# Power_System.net
KiCad netlist of a schematic drawn in Altium Designer
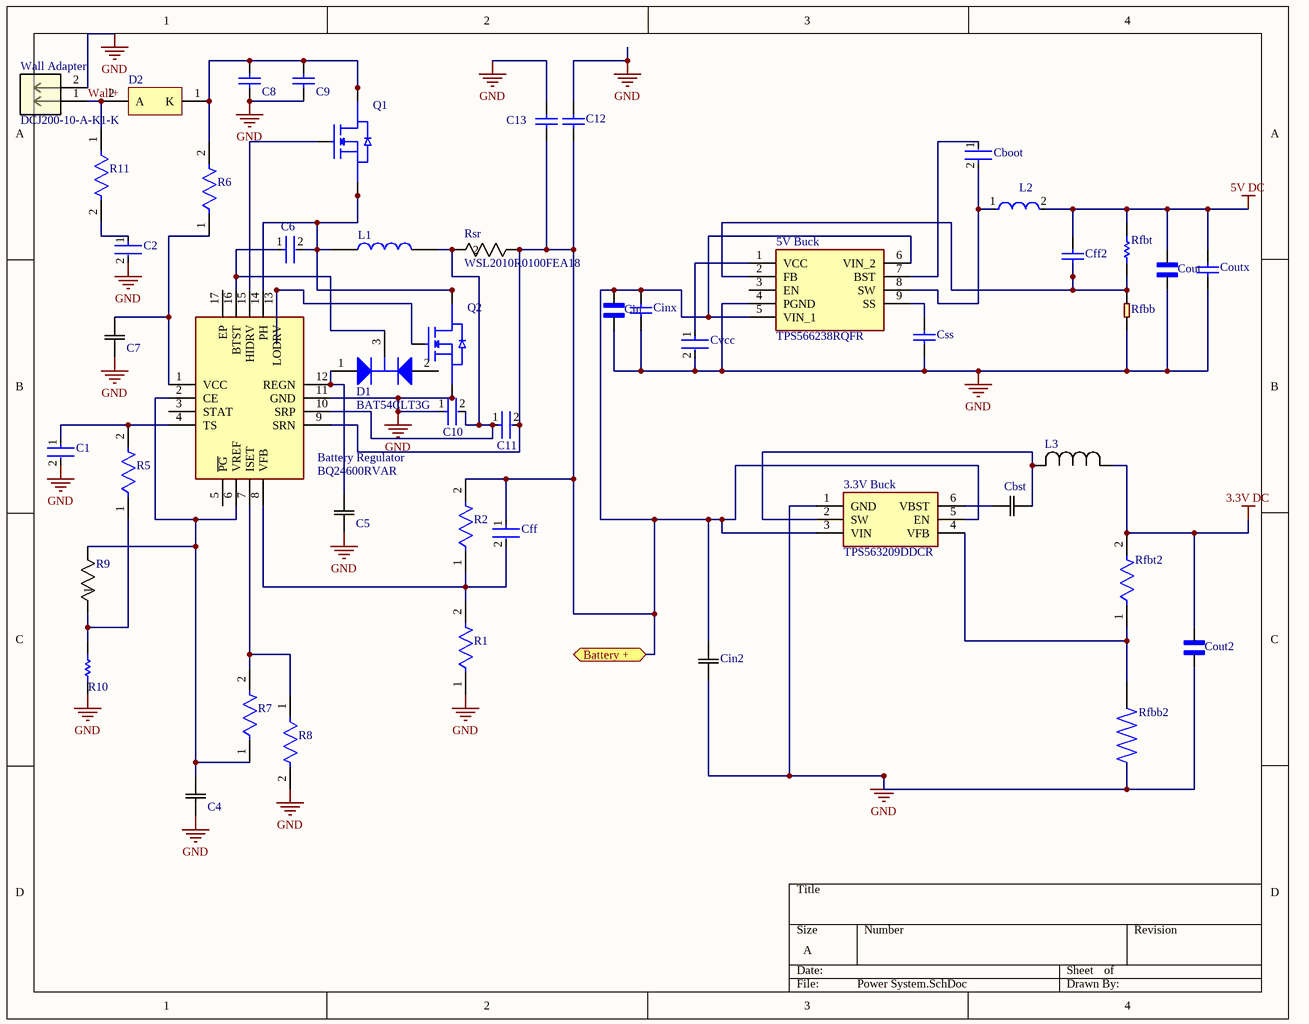
[diagram p0: Power System.SchDoc]

(export (version "E")
  (design (tool "Eeschema 10.0.6"))
  (components
    (comp (ref "3.3V Buck")
      (value "TPS563209DDCR")
      (footprint "SOT95P280X110-6N")
      (description "17 V Input, 3A Synchronous Step-Down Regulator in SOT-23")
      (fields (field (name "MOUSER PART NUMBER") "595-TPS563209DDCR"))
      (libsource (lib "William Jachimiak") (part "TPS563209DDCR"))
    )
    (comp (ref "5V Buck")
      (value "TPS566238RQFR")
      (footprint "TPS566238RQFR")
      (fields (field (name "MOUSER PART NUMBER") "595-TPS566238RQFR"))
      (libsource (lib "William Jachimiak") (part "TPS566238RQFR"))
    )
    (comp (ref "Battery Regulator")
      (value "BQ24600RVAR")
      (footprint "QFN50P350X350X100-17N-D")
      (description "Synchronous Switch-Mode Li-Ion or Li-Polymer Battery Charger")
      (fields (field (name "MOUSER PART NUMBER") "595-BQ24600RVAR"))
      (libsource (lib "William Jachimiak") (part "BQ24600RVAR"))
    )
    (comp (ref "C1")
      (value "C0603C104K4RAC7411")
      (footprint "FP-C0603C-CF-MFG")
      (description "CAP CER 0.1UF 16V X7R 0603")
      (fields (field (name "MANUFACTURER") "KEMET") (field (name "TOLERANCE") "0.1"))
      (libsource (lib "Altium Content Vault") (part "b4654b650e69147ec39a6b967a45e02"))
    )
    (comp (ref "C2")
      (value "CGA5L3X7R1H225K160AB")
      (footprint "FP-CGA5L-0_3-0_1-IPC_C")
      (description "Cap Ceramic 2.2uF 50V X7R 10% Pad SMD 1206 +125°C Automotive T/R")
      (fields (field (name "TOLERANCE") "10%"))
      (libsource (lib "Altium Content Vault") (part "b4654b650e69147ec39a6b967a45e02"))
    )
    (comp (ref "C4")
      (value "C1206C105K4RACTU")
      (footprint "CAPC340180_140N_KEM")
      (description "SMD Comm X7R, Ceramic, 1 uF, 10%, 16 VDC, X7R, SMD, MLCC, Temperature Stable, Class II, 1206")
      (fields (field (name "COPYRIGHT") "Copyright (C) 2025 Ultra Librarian. All rights reserved."))
      (libsource (lib "C1206C105K4RACTU") (part "C1206C105K4RACTU"))
    )
    (comp (ref "C5")
      (value "C1206C105K4RACTU")
      (footprint "CAPC340180_140N_KEM")
      (description "SMD Comm X7R, Ceramic, 1 uF, 10%, 16 VDC, X7R, SMD, MLCC, Temperature Stable, Class II, 1206")
      (fields (field (name "COPYRIGHT") "Copyright (C) 2025 Ultra Librarian. All rights reserved."))
      (libsource (lib "C1206C105K4RACTU") (part "C1206C105K4RACTU"))
    )
    (comp (ref "C6")
      (value "C0603C104K4RAC7411")
      (footprint "FP-C0603C-CF-MFG")
      (description "CAP CER 0.1UF 16V X7R 0603")
      (fields (field (name "MANUFACTURER") "KEMET") (field (name "TOLERANCE") "0.1"))
      (libsource (lib "Altium Content Vault") (part "b4654b650e69147ec39a6b967a45e02"))
    )
    (comp (ref "C7")
      (value "GRM32ER71H105KA01L")
      (footprint "CAP_GRM32ED_MUR")
      (description "No Description Available")
      (fields (field (name "COPYRIGHT") "Copyright (C) 2025 Ultra Librarian. All rights reserved."))
      (libsource (lib "GRM32ER71H105KA01L") (part "GRM32ER71H105KA01L"))
    )
    (comp (ref "C8")
      (value "GRM32ER7YA106KA12L")
      (footprint "CAPC3225X270X30LL30")
      (description "Chip Capacitor, 10 uF, +/- 10%, 35 V, -55 to 125 degC, 1210 (3225 Metric), RoHS, Tape and Reel")
      (fields (field (name "MANUFACTURER") "Murata"))
      (libsource (lib "Altium Content Vault") (part "CAP-NP-2"))
    )
    (comp (ref "C9")
      (value "GRM32ER7YA106KA12L")
      (footprint "CAPC3225X270X30LL30")
      (description "Chip Capacitor, 10 uF, +/- 10%, 35 V, -55 to 125 degC, 1210 (3225 Metric), RoHS, Tape and Reel")
      (fields (field (name "MANUFACTURER") "Murata"))
      (libsource (lib "Altium Content Vault") (part "CAP-NP-2"))
    )
    (comp (ref "C10")
      (value "C0603C104K5RACTU")
      (footprint "FP-C0603C-CF-MFG")
      (description "CAP CER 0.1UF 50V X7R 0603")
      (fields (field (name "TOLERANCE") "0.1") (field (name "MANUFACTURER") "KEMET"))
      (libsource (lib "Altium Content Vault") (part "b4654b650e69147ec39a6b967a45e02"))
    )
    (comp (ref "C11")
      (value "C0603C104K4RAC7411")
      (footprint "FP-C0603C-CF-MFG")
      (description "CAP CER 0.1UF 16V X7R 0603")
      (fields (field (name "MANUFACTURER") "KEMET") (field (name "TOLERANCE") "0.1"))
      (libsource (lib "Altium Content Vault") (part "b4654b650e69147ec39a6b967a45e02"))
    )
    (comp (ref "C12")
      (value "GRM32ER7YA106KA12L")
      (footprint "CAPC3225X270X30LL30")
      (description "Chip Capacitor, 10 uF, +/- 10%, 35 V, -55 to 125 degC, 1210 (3225 Metric), RoHS, Tape and Reel")
      (fields (field (name "MANUFACTURER") "Murata"))
      (libsource (lib "Altium Content Vault") (part "CAP-NP-2"))
    )
    (comp (ref "C13")
      (value "GRM32ER7YA106KA12L")
      (footprint "CAPC3225X270X30LL30")
      (description "Chip Capacitor, 10 uF, +/- 10%, 35 V, -55 to 125 degC, 1210 (3225 Metric), RoHS, Tape and Reel")
      (fields (field (name "MANUFACTURER") "Murata"))
      (libsource (lib "Altium Content Vault") (part "CAP-NP-2"))
    )
    (comp (ref "Cboot")
      (value "GRM155R71C104KA88D")
      (footprint "FP-GRM15-MFG")
      (description "CAP CER 0.1UF 16V X7R 0402")
      (fields
        (field (name "TOLERANCE") "10%")
        (field (name "OCTOPART") "https://octopart.com/grm155r71c104ka88d-murata-196880")
      )
      (libsource (lib "Altium Content Vault") (part "236180d848d6139a670b325ea6854c9"))
    )
    (comp (ref "Cbst")
      (value "08053C104KAT2A")
      (footprint "CAP_X7R_0805_AVX")
      (description "Description")
      (fields (field (name "COPYRIGHT") "Copyright (C) 2025 Ultra Librarian. All rights reserved."))
      (libsource (lib "08053C104KAT2A") (part "08053C104KAT2A"))
    )
    (comp (ref "Cff")
      (value "DE11XRB220KN4AR01F")
      (footprint "FP-DE1_D6_T5_F10_d0_6-0_0-MFG")
      (description "Cap Ceramic Disc 22pF 10% 500VAC Thru-Hole 6.0x5.0x10.0 Ammo pack")
      (libsource (lib "Altium Content Vault") (part "11868f565c42a9108669ba33697ecf6"))
    )
    (comp (ref "Cff2")
      (value "06033A330JAT2A")
      (footprint "CAPC1608X90X35LL15T15")
      (fields (field (name "MANUFACTURER") "AVX Interconnect / Elco"))
      (libsource (lib "Altium Content Vault") (part "CAP"))
    )
    (comp (ref "Cin")
      (value "MSASE21GBB5226MTNA01")
      (footprint "CAPC2012X145N")
      (fields (field (name "MF") "{'manufacturer': u'Taiyo Yuden'}"))
      (libsource (lib "MSASE21GBB5226MTNA01") (part "MSASE21GBB5226MTNA01"))
    )
    (comp (ref "Cin2")
      (value "MSAST219LB5106KTNA01")
      (footprint "CAP_MSAS21-9_TAY")
      (description "Description")
      (fields (field (name "COPYRIGHT") "Copyright (C) 2025 Ultra Librarian. All rights reserved."))
      (libsource (lib "MSAST219LB5106KTNA01") (part "MSAST219LB5106KTNA01"))
    )
    (comp (ref "Cinx")
      (value "GRM188R71H104KA93D")
      (footprint "CAPC1608X90X35ML10T15")
      (description "Chip Capacitor, 0.1 uF, +/- 10%, 50 V, -55 to 125 degC, 0603 (1608 Metric), RoHS, Tape and Reel")
      (fields (field (name "TOLERANCE") "10%") (field (name "VOLTAGE") "50V"))
      (libsource (lib "Altium Content Vault") (part "CAP-NP-2"))
    )
    (comp (ref "Cout")
      (value "LMK212BJ226MG-T")
      (footprint "CAPC2012X135N")
      (fields (field (name "MP") "altium_native_batch"))
      (libsource (lib "LMK212BJ226MG-T") (part "LMK212BJ226MG-T"))
    )
    (comp (ref "Cout2")
      (value "GRM188R60J226MEA0D")
      (footprint "CAPC1608X100N")
      (description "22 ÂµF Â±20% 6.3V Ceramic Capacitor X5R 0603 (1608 Metric)")
      (fields (field (name "MF") "Murata"))
      (libsource (lib "GRM188R60J226MEA0D") (part "GRM188R60J226MEA0D"))
    )
    (comp (ref "Coutx")
      (value "GRM188R71E104KA01D")
      (footprint "CAPC1608X90X35LL10T15")
      (fields (field (name "MANUFACTURER") "Murata"))
      (libsource (lib "Altium Content Vault") (part "CAP"))
    )
    (comp (ref "Css")
      (value "GRM155R71C103KA01D")
      (footprint "CAPC1005X55X25LL05T10")
      (description "Chip Capacitor, 10 nF, 16 V, 10%, -55 to 125 degC, 0402 (1005 Metric), RoHS, Tape and Reel")
      (fields (field (name "MANUFACTURER") "Murata"))
      (libsource (lib "Altium Content Vault") (part "CAP-NP-2"))
    )
    (comp (ref "Cvcc")
      (value "EMK107B7105KA-T")
      (footprint "FP-0603-L_1_6_0_1-W_0_8_0-IPC_C")
      (description "None")
      (fields (field (name "TOLERANCE") "10%"))
      (libsource (lib "Altium Content Vault") (part "02cd4be3c70576c341d710602a673aa"))
    )
    (comp (ref "D1")
      (value "BAT54CLT3G")
      (footprint "ONSC-SOT-23-3-318-08_V")
      (description "Dual Common Cathode Schottky Barrier Diodes, 3-Pin SOT-23, Pb-Free, Tape and Reel")
      (fields (field (name "MANUFACTURER") "On Semiconductor"))
      (libsource (lib "Altium Content Vault") (part "ONSC-D-A1A2K3-3"))
    )
    (comp (ref "D2")
      (value "MBRS540T3G")
      (footprint "ONSC-SMC-2-403-03_V")
      (description "Schottky Power Rectifier, 2-Pin SMC, Pb-Free, Tape and Reel")
      (fields (field (name "MANUFACTURER") "On Semiconductor"))
      (libsource (lib "Altium Content Vault") (part "ONSC-D-K1A2-2_A"))
    )
    (comp (ref "L1")
      (value "IHLP2525CZER3R3MA1")
      (footprint "INDPM6965X300N")
      (description "Power Choke Shielded Wirewound 3.3uH 20% 100KHz Powdered Iron 6A 0.03Ohm DCR 2525 Automotive T/R")
      (fields (field (name "MOUSER PART NUMBER") "70-IHLP2525CZR3R3MA1"))
      (libsource (lib "IHLP2525CZER3R3MA1") (part "IHLP2525CZER3R3MA1"))
    )
    (comp (ref "L2")
      (value "XAL5030-222MEB")
      (footprint "FP-XAL5030-222MEB-MFG")
      (description "Fixed Inductors 2.2uH 20% 9.7A 14.5mOhms")
      (fields (field (name "TOLERANCE") "20%"))
      (libsource (lib "Altium Content Vault") (part "725321dda6339637d4d059423bc1c3c"))
    )
    (comp (ref "L3")
      (value "SRN8040-2R2Y")
      (footprint "IND_BOURNS_SRN8040")
      (description "Description")
      (fields (field (name "COPYRIGHT") "Copyright (C) 2025 Ultra Librarian. All rights reserved."))
      (libsource (lib "SRN8040-2R2Y") (part "SRN8040-2R2Y"))
    )
    (comp (ref "Q1")
      (value "SIR426DP-T1-GE3")
      (footprint "TRANS_SIRA90DP-T1-GE3")
      (description "40V 30A 41.7W 10.5mohm @ 10V ¦ Siliconix / Vishay SIR426DP-T1-GE3")
      (fields (field (name "MF") "Vishay Siliconix"))
      (libsource (lib "SIR426DP-T1-GE3") (part "SIR426DP-T1-GE3"))
    )
    (comp (ref "Q2")
      (value "SIR426DP-T1-GE3")
      (footprint "TRANS_SIRA90DP-T1-GE3")
      (description "40V 30A 41.7W 10.5mohm @ 10V ¦ Siliconix / Vishay SIR426DP-T1-GE3")
      (fields (field (name "MF") "Vishay Siliconix"))
      (libsource (lib "SIR426DP-T1-GE3") (part "SIR426DP-T1-GE3"))
    )
    (comp (ref "R1")
      (value "RR0816P-104-D")
      (footprint "FP-RR0816-IPC_A")
      (description "100kΩ ±0.5% 0.0625W 1/16W Chip Resistor 0603 (1608 Metric) Thin Film")
      (fields (field (name "TOLERANCE") "0.5%"))
      (libsource (lib "Altium Content Vault") (part "1029c3af85768c4190bb7ad29bc67b5"))
    )
    (comp (ref "R2")
      (value "RR0816P-304-D")
      (footprint "FP-RR0816-IPC_C")
      (description "300kΩ ±0.5% 0.0625W 1/16W Chip Resistor 0603 (1608 Metric) Thin Film")
      (fields (field (name "TOLERANCE") "0.5%"))
      (libsource (lib "Altium Content Vault") (part "1029c3af85768c4190bb7ad29bc67b5"))
    )
    (comp (ref "R5")
      (value "RR0816P-101-D")
      (footprint "FP-RR0816-MFG")
      (description "100Ω ±0.5% 0.0625W 1/16W Chip Resistor 0603 (1608 Metric) Thin Film")
      (fields (field (name "TOLERANCE") "0.5%"))
      (libsource (lib "Altium Content Vault") (part "1029c3af85768c4190bb7ad29bc67b5"))
    )
    (comp (ref "R6")
      (value "RMCF2512JT10R0")
      (footprint "FP-RMCF2512-IPC_B")
      (description "10Ω ±5% 1W 2512 Thick Film Chip Resistor AEC-Q200 compliant")
      (fields (field (name "TOLERANCE") "5%"))
      (libsource (lib "Altium Content Vault") (part "1029c3af85768c4190bb7ad29bc67b5"))
    )
    (comp (ref "R7")
      (value "RR0816P-104-D")
      (footprint "FP-RR0816-IPC_A")
      (description "100kΩ ±0.5% 0.0625W 1/16W Chip Resistor 0603 (1608 Metric) Thin Film")
      (fields (field (name "TOLERANCE") "0.5%"))
      (libsource (lib "Altium Content Vault") (part "1029c3af85768c4190bb7ad29bc67b5"))
    )
    (comp (ref "R8")
      (value "RR0816P-154-D")
      (footprint "FP-RR0816-IPC_C")
      (description "150kΩ ±0.5% 0.0625W 1/16W Chip Resistor 0603 (1608 Metric) Thin Film")
      (fields (field (name "TOLERANCE") "0.5%"))
      (libsource (lib "Altium Content Vault") (part "1029c3af85768c4190bb7ad29bc67b5"))
    )
    (comp (ref "R9")
      (value "RMCF0402FT9K31")
      (footprint "RES_RMCF0402_STP")
      (description "No Description Available")
      (fields (field (name "COPYRIGHT") "Copyright (C) 2025 Ultra Librarian. All rights reserved."))
      (libsource (lib "RMCF0402FT9K31") (part "RMCF0402FT9K31"))
    )
    (comp (ref "R10")
      (value "RC0402FR-07442KL")
      (footprint "RESC1005X40X25LL05T10")
      (fields (field (name "MANUFACTURER") "Yageo / Phycomp"))
      (libsource (lib "Altium Content Vault") (part "RES"))
    )
    (comp (ref "R11")
      (value "RMCF2512JT2R00")
      (footprint "FP-RMCF2512-IPC_A")
      (description "2Ω ±5% 1W 2512 Thick Film Chip Resistor AEC-Q200 compliant")
      (fields (field (name "TOLERANCE") "5%"))
      (libsource (lib "Altium Content Vault") (part "1029c3af85768c4190bb7ad29bc67b5"))
    )
    (comp (ref "Rfbb")
      (value "SMD-RES-30K-1%-1/10W(0603)")
      (footprint "R0603")
      (description "30 kOhms Â±1% 0.1W, 1/10W Chip Resistor 0603 (1608 Metric) Moisture Resistant Thick Film")
      (fields (field (name "MF") "Yageo") (field (name "MP") "RC0603FR-0730KL"))
      (libsource (lib "SMD-RES-30K-1%-1_10W(0603)") (part "SMD-RES-30K-1%-1/10W(0603)"))
    )
    (comp (ref "Rfbb2")
      (value "M55342K11B10E0RS3")
      (footprint "RESC0905X41N")
      (libsource (lib "M55342K11B10E0RS3") (part "M55342K11B10E0RS3"))
    )
    (comp (ref "Rfbt")
      (value "RC0603FR-07220KL")
      (footprint "RESC1608X55X25ML10T15")
      (description "Chip Resistor, 220 KOhm, +/- 1%, 100 mW, -55 to 155 degC, 0603 (1608 Metric), RoHS, Tape and Reel")
      (libsource (lib "Altium Content Vault") (part "RES-2"))
    )
    (comp (ref "Rfbt2")
      (value "CRCW040233K2FKED")
      (footprint "Vishay_CRCW0402-e3_MFG")
      (fields (field (name "TOLERANCE") "1%"))
      (libsource (lib "Altium Content Vault") (part "CRCW040233K2FKED"))
    )
    (comp (ref "Rsr")
      (value "WSL2010R0100FEA18")
      (footprint "RC2010N_VIS")
      (description "WSL-2010-18 .01 1% EA e3")
      (fields (field (name "COPYRIGHT") "Copyright (C) 2025 Ultra Librarian. All rights reserved."))
      (libsource (lib "WSL2010R0100FEA18") (part "WSL2010R0100FEA18"))
    )
    (comp (ref "Wall Adapter")
      (value "DCJ200-10-A-K1-K")
      (footprint "CONN3_DCJ200-10-A-K1-K_GCT")
      (description "Description")
      (fields (field (name "COPYRIGHT") "Copyright (C) 2025 Ultra Librarian. All rights reserved."))
      (libsource (lib "DCJ200-10-A-K1-K") (part "DCJ200-10-A-K1-K"))
    )
  )
  (nets
    (net (code "1") (name "/Battery +") (class "Default")
      (node (ref "3.3V Buck") (pin "3") (pinfunction "VIN_3") (pintype "passive"))
      (node (ref "3.3V Buck") (pin "5") (pinfunction "EN_5") (pintype "passive"))
      (node (ref "5V Buck") (pin "5") (pinfunction "VIN_1_5") (pintype "passive"))
      (node (ref "5V Buck") (pin "6") (pinfunction "VIN_2_6") (pintype "passive"))
      (node (ref "Battery Regulator") (pin "9") (pinfunction "SRN_9") (pintype "passive"))
      (node (ref "C11") (pin "2") (pinfunction "2_2") (pintype "passive"))
      (node (ref "C12") (pin "1") (pinfunction "1_1") (pintype "passive"))
      (node (ref "C13") (pin "1") (pinfunction "1_1") (pintype "passive"))
      (node (ref "Cff") (pin "1") (pinfunction "1_1") (pintype "passive"))
      (node (ref "Cin") (pin "2") (pinfunction "2_2") (pintype "passive"))
      (node (ref "Cin2") (pin "2") (pinfunction "2_2") (pintype "passive"))
      (node (ref "Cinx") (pin "2") (pinfunction "2_2") (pintype "passive"))
      (node (ref "R2") (pin "2") (pinfunction "2_2") (pintype "passive"))
      (node (ref "Rsr") (pin "1") (pinfunction "1_1") (pintype "passive"))
    )
    (net (code "2") (name "/Wall+") (class "Default")
      (node (ref "D2") (pin "2") (pinfunction "A_2") (pintype "passive"))
      (node (ref "R11") (pin "1") (pinfunction "1_1") (pintype "passive"))
      (node (ref "Wall Adapter") (pin "1") (pinfunction "1_1") (pintype "passive"))
    )
    (net (code "3") (name "3.3V DC") (class "Default")
      (node (ref "Cout2") (pin "2") (pinfunction "2_2") (pintype "passive"))
      (node (ref "L3") (pin "1") (pinfunction "1_1") (pintype "passive"))
      (node (ref "Rfbt2") (pin "2") (pinfunction "2_2") (pintype "passive"))
    )
    (net (code "4") (name "5V DC") (class "Default")
      (node (ref "Cff2") (pin "2") (pinfunction "2_2") (pintype "passive"))
      (node (ref "Cout") (pin "2") (pinfunction "2_2") (pintype "passive"))
      (node (ref "Coutx") (pin "2") (pinfunction "2_2") (pintype "passive"))
      (node (ref "L2") (pin "2") (pinfunction "2_2") (pintype "passive"))
      (node (ref "Rfbt") (pin "2") (pinfunction "2_2") (pintype "passive"))
    )
    (net (code "5") (name "GND") (class "Default")
      (node (ref "3.3V Buck") (pin "1") (pinfunction "GND_1") (pintype "passive"))
      (node (ref "5V Buck") (pin "4") (pinfunction "PGND_4") (pintype "passive"))
      (node (ref "Battery Regulator") (pin "11") (pinfunction "GND_11") (pintype "passive"))
      (node (ref "C1") (pin "2") (pinfunction "2_2") (pintype "passive"))
      (node (ref "C10") (pin "1") (pinfunction "1_1") (pintype "passive"))
      (node (ref "C12") (pin "2") (pinfunction "2_2") (pintype "passive"))
      (node (ref "C13") (pin "2") (pinfunction "2_2") (pintype "passive"))
      (node (ref "C2") (pin "2") (pinfunction "2_2") (pintype "passive"))
      (node (ref "C4") (pin "1") (pinfunction "1_1") (pintype "passive"))
      (node (ref "C5") (pin "1") (pinfunction "1_1") (pintype "passive"))
      (node (ref "C7") (pin "1") (pinfunction "1_1") (pintype "passive"))
      (node (ref "C8") (pin "1") (pinfunction "1_1") (pintype "passive"))
      (node (ref "C9") (pin "1") (pinfunction "1_1") (pintype "passive"))
      (node (ref "Cin") (pin "1") (pinfunction "1_1") (pintype "passive"))
      (node (ref "Cin2") (pin "1") (pinfunction "1_1") (pintype "passive"))
      (node (ref "Cinx") (pin "1") (pinfunction "1_1") (pintype "passive"))
      (node (ref "Cout") (pin "1") (pinfunction "1_1") (pintype "passive"))
      (node (ref "Cout2") (pin "1") (pinfunction "1_1") (pintype "passive"))
      (node (ref "Coutx") (pin "1") (pinfunction "1_1") (pintype "passive"))
      (node (ref "Css") (pin "1") (pinfunction "1_1") (pintype "passive"))
      (node (ref "Cvcc") (pin "2") (pinfunction "2_2") (pintype "passive"))
      (node (ref "Q2") (pin "1") (pinfunction "S_1") (pintype "passive"))
      (node (ref "Q2") (pin "2") (pinfunction "S_2") (pintype "passive"))
      (node (ref "Q2") (pin "3") (pinfunction "S_3") (pintype "passive"))
      (node (ref "R1") (pin "1") (pinfunction "1_1") (pintype "passive"))
      (node (ref "R10") (pin "1") (pinfunction "1_1") (pintype "passive"))
      (node (ref "R8") (pin "2") (pinfunction "2_2") (pintype "passive"))
      (node (ref "Rfbb") (pin "1") (pinfunction "1_1") (pintype "passive"))
      (node (ref "Rfbb2") (pin "1") (pinfunction "1_1") (pintype "passive"))
      (node (ref "Wall Adapter") (pin "2") (pinfunction "2_2") (pintype "passive"))
    )
    (net (code "6") (name "Net-(3.3V Buck-SW)") (class "Default")
      (node (ref "3.3V Buck") (pin "2") (pinfunction "SW_2") (pintype "passive"))
      (node (ref "Cbst") (pin "2") (pinfunction "2_2") (pintype "passive"))
      (node (ref "L3") (pin "2") (pinfunction "2_2") (pintype "passive"))
    )
    (net (code "7") (name "Net-(3.3V Buck-VBST)") (class "Default")
      (node (ref "3.3V Buck") (pin "6") (pinfunction "VBST_6") (pintype "passive"))
      (node (ref "Cbst") (pin "1") (pinfunction "1_1") (pintype "passive"))
    )
    (net (code "8") (name "Net-(3.3V Buck-VFB)") (class "Default")
      (node (ref "3.3V Buck") (pin "4") (pinfunction "VFB_4") (pintype "passive"))
      (node (ref "Rfbb2") (pin "2") (pinfunction "2_2") (pintype "passive"))
      (node (ref "Rfbt2") (pin "1") (pinfunction "1_1") (pintype "passive"))
    )
    (net (code "9") (name "Net-(5V Buck-BST)") (class "Default")
      (node (ref "5V Buck") (pin "7") (pinfunction "BST_7") (pintype "passive"))
      (node (ref "Cboot") (pin "1") (pinfunction "1_1") (pintype "passive"))
    )
    (net (code "10") (name "Net-(5V Buck-FB)") (class "Default")
      (node (ref "5V Buck") (pin "2") (pinfunction "FB_2") (pintype "passive"))
      (node (ref "Cff2") (pin "1") (pinfunction "1_1") (pintype "passive"))
      (node (ref "Rfbb") (pin "2") (pinfunction "2_2") (pintype "passive"))
      (node (ref "Rfbt") (pin "1") (pinfunction "1_1") (pintype "passive"))
    )
    (net (code "11") (name "Net-(5V Buck-SS)") (class "Default")
      (node (ref "5V Buck") (pin "9") (pinfunction "SS_9") (pintype "passive"))
      (node (ref "Css") (pin "2") (pinfunction "2_2") (pintype "passive"))
    )
    (net (code "12") (name "Net-(5V Buck-SW)") (class "Default")
      (node (ref "5V Buck") (pin "8") (pinfunction "SW_8") (pintype "passive"))
      (node (ref "Cboot") (pin "2") (pinfunction "2_2") (pintype "passive"))
      (node (ref "L2") (pin "1") (pinfunction "1_1") (pintype "passive"))
    )
    (net (code "13") (name "Net-(5V Buck-VCC)") (class "Default")
      (node (ref "5V Buck") (pin "1") (pinfunction "VCC_1") (pintype "passive"))
      (node (ref "Cvcc") (pin "1") (pinfunction "1_1") (pintype "passive"))
    )
    (net (code "14") (name "Net-(Battery Regulator-BTST)") (class "Default")
      (node (ref "Battery Regulator") (pin "16") (pinfunction "BTST_16") (pintype "passive"))
      (node (ref "C6") (pin "1") (pinfunction "1_1") (pintype "passive"))
      (node (ref "D1") (pin "3") (pinfunction "K_3") (pintype "passive"))
    )
    (net (code "15") (name "Net-(Battery Regulator-CE)") (class "Default")
      (node (ref "Battery Regulator") (pin "2") (pinfunction "CE_2") (pintype "passive"))
      (node (ref "Battery Regulator") (pin "6") (pinfunction "VREF_6") (pintype "passive"))
      (node (ref "C4") (pin "2") (pinfunction "2_2") (pintype "passive"))
      (node (ref "R7") (pin "1") (pinfunction "1_1") (pintype "passive"))
      (node (ref "R9") (pin "2") (pinfunction "2_2") (pintype "passive"))
    )
    (net (code "16") (name "Net-(Battery Regulator-HIDRV)") (class "Default")
      (node (ref "Battery Regulator") (pin "15") (pinfunction "HIDRV_15") (pintype "passive"))
      (node (ref "Q1") (pin "4") (pinfunction "G_4") (pintype "passive"))
    )
    (net (code "17") (name "Net-(Battery Regulator-ISET)") (class "Default")
      (node (ref "Battery Regulator") (pin "7") (pinfunction "ISET_7") (pintype "passive"))
      (node (ref "R7") (pin "2") (pinfunction "2_2") (pintype "passive"))
      (node (ref "R8") (pin "1") (pinfunction "1_1") (pintype "passive"))
    )
    (net (code "18") (name "Net-(Battery Regulator-LODRV)") (class "Default")
      (node (ref "Battery Regulator") (pin "13") (pinfunction "LODRV_13") (pintype "passive"))
      (node (ref "Q2") (pin "4") (pinfunction "G_4") (pintype "passive"))
    )
    (net (code "19") (name "Net-(Battery Regulator-PH)") (class "Default")
      (node (ref "Battery Regulator") (pin "14") (pinfunction "PH_14") (pintype "passive"))
      (node (ref "C6") (pin "2") (pinfunction "2_2") (pintype "passive"))
      (node (ref "L1") (pin "1") (pinfunction "1_1") (pintype "passive"))
      (node (ref "Q1") (pin "1") (pinfunction "S_1") (pintype "passive"))
      (node (ref "Q1") (pin "2") (pinfunction "S_2") (pintype "passive"))
      (node (ref "Q1") (pin "3") (pinfunction "S_3") (pintype "passive"))
      (node (ref "Q2") (pin "5") (pinfunction "D_5") (pintype "passive"))
      (node (ref "Q2") (pin "6") (pinfunction "D_6") (pintype "passive"))
      (node (ref "Q2") (pin "7") (pinfunction "D_7") (pintype "passive"))
      (node (ref "Q2") (pin "8") (pinfunction "D_8") (pintype "passive"))
      (node (ref "Q2") (pin "9") (pinfunction "D_9") (pintype "passive"))
    )
    (net (code "20") (name "Net-(Battery Regulator-REGN)") (class "Default")
      (node (ref "Battery Regulator") (pin "12") (pinfunction "REGN_12") (pintype "passive"))
      (node (ref "C5") (pin "2") (pinfunction "2_2") (pintype "passive"))
      (node (ref "D1") (pin "1") (pinfunction "A1_1") (pintype "passive"))
    )
    (net (code "21") (name "Net-(Battery Regulator-SRP)") (class "Default")
      (node (ref "Battery Regulator") (pin "10") (pinfunction "SRP_10") (pintype "passive"))
      (node (ref "C10") (pin "2") (pinfunction "2_2") (pintype "passive"))
      (node (ref "C11") (pin "1") (pinfunction "1_1") (pintype "passive"))
      (node (ref "L1") (pin "2") (pinfunction "2_2") (pintype "passive"))
      (node (ref "Rsr") (pin "2") (pinfunction "2_2") (pintype "passive"))
    )
    (net (code "22") (name "Net-(Battery Regulator-TS)") (class "Default")
      (node (ref "Battery Regulator") (pin "4") (pinfunction "TS_4") (pintype "passive"))
      (node (ref "C1") (pin "1") (pinfunction "1_1") (pintype "passive"))
      (node (ref "R5") (pin "2") (pinfunction "2_2") (pintype "passive"))
    )
    (net (code "23") (name "Net-(Battery Regulator-VCC)") (class "Default")
      (node (ref "Battery Regulator") (pin "1") (pinfunction "VCC_1") (pintype "passive"))
      (node (ref "C7") (pin "2") (pinfunction "2_2") (pintype "passive"))
      (node (ref "R6") (pin "1") (pinfunction "1_1") (pintype "passive"))
    )
    (net (code "24") (name "Net-(Battery Regulator-VFB)") (class "Default")
      (node (ref "Battery Regulator") (pin "8") (pinfunction "VFB_8") (pintype "passive"))
      (node (ref "Cff") (pin "2") (pinfunction "2_2") (pintype "passive"))
      (node (ref "R1") (pin "2") (pinfunction "2_2") (pintype "passive"))
      (node (ref "R2") (pin "1") (pinfunction "1_1") (pintype "passive"))
    )
    (net (code "25") (name "Net-(C2-Pad1)") (class "Default")
      (node (ref "C2") (pin "1") (pinfunction "1_1") (pintype "passive"))
      (node (ref "R11") (pin "2") (pinfunction "2_2") (pintype "passive"))
    )
    (net (code "26") (name "Net-(D2-K)") (class "Default")
      (node (ref "C8") (pin "2") (pinfunction "2_2") (pintype "passive"))
      (node (ref "C9") (pin "2") (pinfunction "2_2") (pintype "passive"))
      (node (ref "D2") (pin "1") (pinfunction "K_1") (pintype "passive"))
      (node (ref "Q1") (pin "5") (pinfunction "D_5") (pintype "passive"))
      (node (ref "Q1") (pin "6") (pinfunction "D_6") (pintype "passive"))
      (node (ref "Q1") (pin "7") (pinfunction "D_7") (pintype "passive"))
      (node (ref "Q1") (pin "8") (pinfunction "D_8") (pintype "passive"))
      (node (ref "Q1") (pin "9") (pinfunction "D_9") (pintype "passive"))
      (node (ref "R6") (pin "2") (pinfunction "2_2") (pintype "passive"))
    )
    (net (code "27") (name "Net-(R10-Pad2)") (class "Default")
      (node (ref "R10") (pin "2") (pinfunction "2_2") (pintype "passive"))
      (node (ref "R5") (pin "1") (pinfunction "1_1") (pintype "passive"))
      (node (ref "R9") (pin "1") (pinfunction "1_1") (pintype "passive"))
    )
    (net (code "28") (name "unconnected-(5V Buck-EN-Pad3)") (class "Default")
      (node (ref "5V Buck") (pin "3") (pinfunction "EN_3") (pintype "passive"))
    )
    (net (code "29") (name "unconnected-(Battery Regulator-EP-Pad17)") (class "Default")
      (node (ref "Battery Regulator") (pin "17") (pinfunction "EP_17") (pintype "passive"))
    )
    (net (code "30") (name "unconnected-(Battery Regulator-STAT-Pad3)") (class "Default")
      (node (ref "Battery Regulator") (pin "3") (pinfunction "STAT_3") (pintype "passive"))
    )
    (net (code "31") (name "unconnected-(Battery Regulator-~{PG}-Pad5)") (class "Default")
      (node (ref "Battery Regulator") (pin "5") (pinfunction "~{PG}_5") (pintype "passive"))
    )
    (net (code "32") (name "unconnected-(D1-A2-Pad2)") (class "Default")
      (node (ref "D1") (pin "2") (pinfunction "A2_2") (pintype "passive"))
    )
  )
)
